# led_flasher_v1.net
KiCad netlist of a schematic drawn in EAGLE
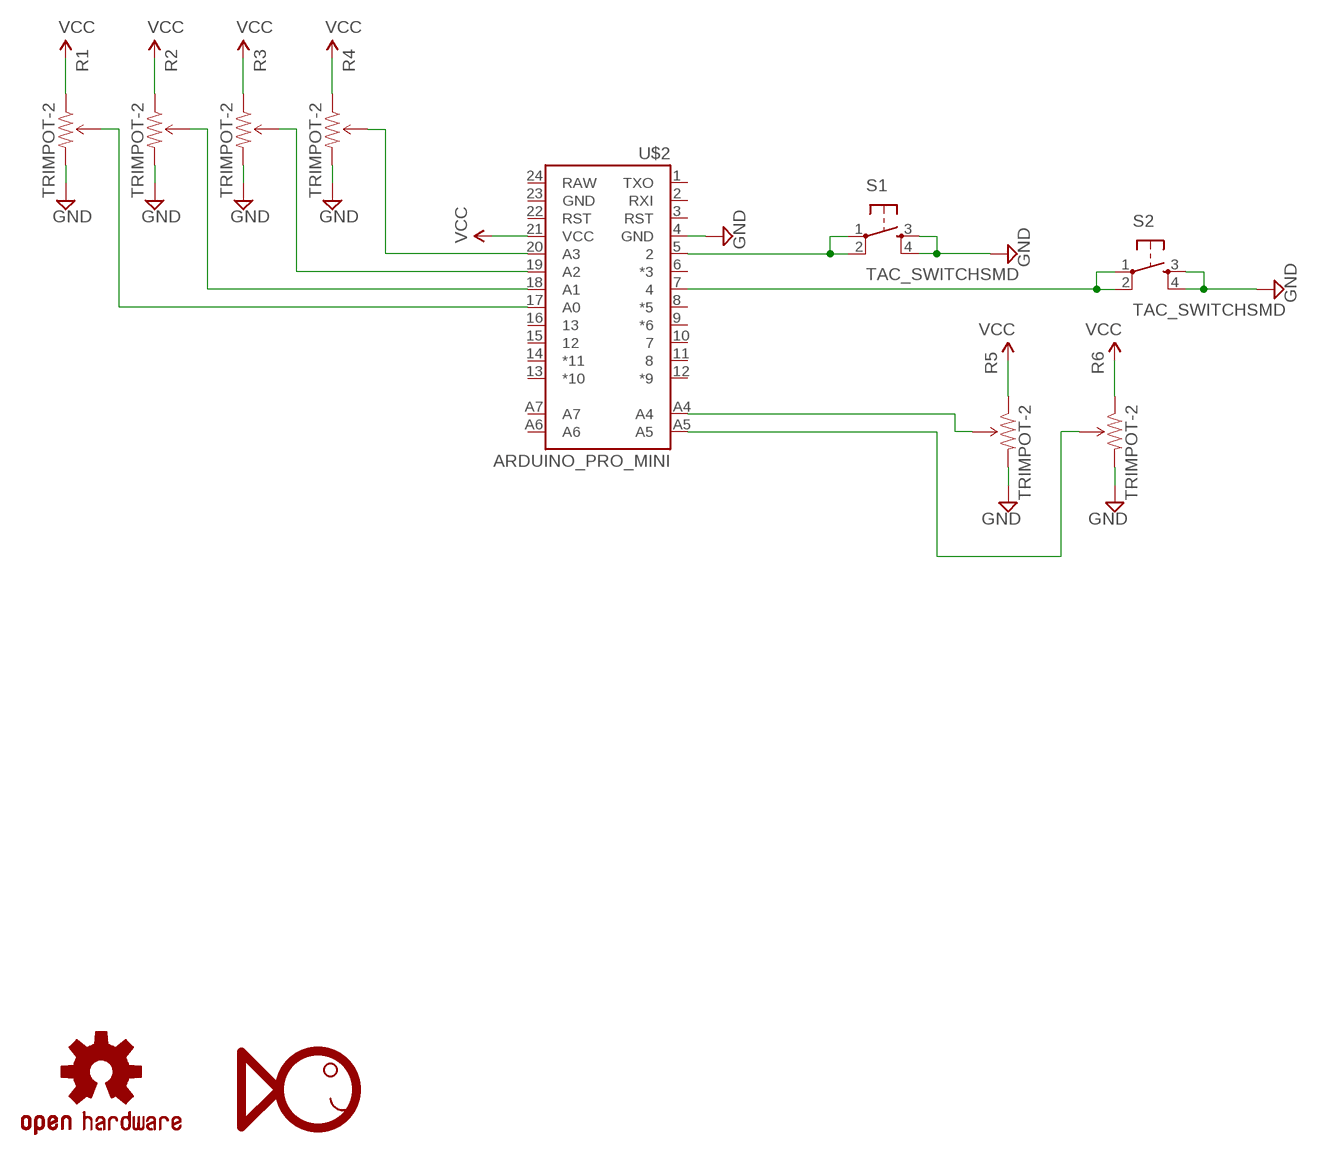
[diagram p0: schematic, sheet 1]

(export (version "E")
  (design (tool "Eeschema 10.0.6"))
  (components
    (comp (ref "LOGO1")
      (value "OSHW-LOGOS")
      (footprint "eagle-import:OSHW-LOGO-S")
      (libsource (lib "eagle-import") (part "OSHW-LOGOS"))
    )
    (comp (ref "R1")
      (value "TRIMPOT-2")
      (footprint "eagle-import:TRIMPOT_TC33")
      (libsource (lib "eagle-import") (part "TRIMPOT-2"))
    )
    (comp (ref "R2")
      (value "TRIMPOT-2")
      (footprint "eagle-import:TRIMPOT_TC33")
      (libsource (lib "eagle-import") (part "TRIMPOT-2"))
    )
    (comp (ref "R3")
      (value "TRIMPOT-2")
      (footprint "eagle-import:TRIMPOT_TC33")
      (libsource (lib "eagle-import") (part "TRIMPOT-2"))
    )
    (comp (ref "R4")
      (value "TRIMPOT-2")
      (footprint "eagle-import:TRIMPOT_TC33")
      (libsource (lib "eagle-import") (part "TRIMPOT-2"))
    )
    (comp (ref "R5")
      (value "TRIMPOT-2")
      (footprint "eagle-import:TRIMPOT_TC33")
      (libsource (lib "eagle-import") (part "TRIMPOT-2"))
    )
    (comp (ref "R6")
      (value "TRIMPOT-2")
      (footprint "eagle-import:TRIMPOT_TC33")
      (libsource (lib "eagle-import") (part "TRIMPOT-2"))
    )
    (comp (ref "S1")
      (value "TAC_SWITCHSMD")
      (footprint "eagle-import:TACTILE-SWITCH-SMD")
      (libsource (lib "eagle-import") (part "TAC_SWITCHSMD"))
    )
    (comp (ref "S2")
      (value "TAC_SWITCHSMD")
      (footprint "eagle-import:TACTILE-SWITCH-SMD")
      (libsource (lib "eagle-import") (part "TAC_SWITCHSMD"))
    )
    (comp (ref "U$1")
      (value "FHI_LOGO")
      (footprint "eagle-import:FHI_LOGO")
      (libsource (lib "eagle-import") (part "FHI_LOGO"))
    )
    (comp (ref "U$2")
      (value "ARDUINO_PRO_MINI")
      (footprint "eagle-import:ARDUINO_PRO_MINI")
      (libsource (lib "eagle-import") (part "ARDUINO_PRO_MINI"))
    )
  )
  (nets
    (net (code "1") (name "GND") (class "Default")
      (node (ref "R1") (pin "3") (pinfunction "CW_3") (pintype "passive"))
      (node (ref "R2") (pin "3") (pinfunction "CW_3") (pintype "passive"))
      (node (ref "R3") (pin "3") (pinfunction "CW_3") (pintype "passive"))
      (node (ref "R4") (pin "3") (pinfunction "CW_3") (pintype "passive"))
      (node (ref "R5") (pin "3") (pinfunction "CW_3") (pintype "passive"))
      (node (ref "R6") (pin "3") (pinfunction "CW_3") (pintype "passive"))
      (node (ref "S1") (pin "3") (pinfunction "3_3") (pintype "passive"))
      (node (ref "S1") (pin "4") (pinfunction "4_4") (pintype "passive"))
      (node (ref "S2") (pin "3") (pinfunction "3_3") (pintype "passive"))
      (node (ref "S2") (pin "4") (pinfunction "4_4") (pintype "passive"))
      (node (ref "U$2") (pin "4") (pinfunction "GND_4") (pintype "bidirectional"))
    )
    (net (code "2") (name "Net-(R1-WIPER)") (class "Default")
      (node (ref "R1") (pin "2") (pinfunction "WIPER_2") (pintype "passive"))
      (node (ref "U$2") (pin "17") (pinfunction "A0_17") (pintype "bidirectional"))
    )
    (net (code "3") (name "Net-(R2-WIPER)") (class "Default")
      (node (ref "R2") (pin "2") (pinfunction "WIPER_2") (pintype "passive"))
      (node (ref "U$2") (pin "18") (pinfunction "A1_18") (pintype "bidirectional"))
    )
    (net (code "4") (name "Net-(R3-WIPER)") (class "Default")
      (node (ref "R3") (pin "2") (pinfunction "WIPER_2") (pintype "passive"))
      (node (ref "U$2") (pin "19") (pinfunction "A2_19") (pintype "bidirectional"))
    )
    (net (code "5") (name "Net-(R4-WIPER)") (class "Default")
      (node (ref "R4") (pin "2") (pinfunction "WIPER_2") (pintype "passive"))
      (node (ref "U$2") (pin "20") (pinfunction "A3_20") (pintype "bidirectional"))
    )
    (net (code "6") (name "Net-(R5-WIPER)") (class "Default")
      (node (ref "R5") (pin "2") (pinfunction "WIPER_2") (pintype "passive"))
      (node (ref "U$2") (pin "A4") (pinfunction "A4_A4") (pintype "bidirectional"))
    )
    (net (code "7") (name "Net-(R6-WIPER)") (class "Default")
      (node (ref "R6") (pin "2") (pinfunction "WIPER_2") (pintype "passive"))
      (node (ref "U$2") (pin "A5") (pinfunction "A5_A5") (pintype "bidirectional"))
    )
    (net (code "8") (name "Net-(U$2-2)") (class "Default")
      (node (ref "S1") (pin "1") (pinfunction "1_1") (pintype "passive"))
      (node (ref "S1") (pin "2") (pinfunction "2_2") (pintype "passive"))
      (node (ref "U$2") (pin "5") (pinfunction "2_5") (pintype "bidirectional"))
    )
    (net (code "9") (name "Net-(U$2-4)") (class "Default")
      (node (ref "S2") (pin "1") (pinfunction "1_1") (pintype "passive"))
      (node (ref "S2") (pin "2") (pinfunction "2_2") (pintype "passive"))
      (node (ref "U$2") (pin "7") (pinfunction "4_7") (pintype "bidirectional"))
    )
    (net (code "10") (name "VCC") (class "Default")
      (node (ref "R1") (pin "1") (pinfunction "CCW_1") (pintype "passive"))
      (node (ref "R2") (pin "1") (pinfunction "CCW_1") (pintype "passive"))
      (node (ref "R3") (pin "1") (pinfunction "CCW_1") (pintype "passive"))
      (node (ref "R4") (pin "1") (pinfunction "CCW_1") (pintype "passive"))
      (node (ref "R5") (pin "1") (pinfunction "CCW_1") (pintype "passive"))
      (node (ref "R6") (pin "1") (pinfunction "CCW_1") (pintype "passive"))
      (node (ref "U$2") (pin "21") (pinfunction "VCC_21") (pintype "bidirectional"))
    )
    (net (code "11") (name "unconnected-(U$2-*3-Pad6)") (class "Default")
      (node (ref "U$2") (pin "6") (pinfunction "*3_6") (pintype "bidirectional"))
    )
    (net (code "12") (name "unconnected-(U$2-*5-Pad8)") (class "Default")
      (node (ref "U$2") (pin "8") (pinfunction "*5_8") (pintype "bidirectional"))
    )
    (net (code "13") (name "unconnected-(U$2-*6-Pad9)") (class "Default")
      (node (ref "U$2") (pin "9") (pinfunction "*6_9") (pintype "bidirectional"))
    )
    (net (code "14") (name "unconnected-(U$2-*9-Pad12)") (class "Default")
      (node (ref "U$2") (pin "12") (pinfunction "*9_12") (pintype "bidirectional"))
    )
    (net (code "15") (name "unconnected-(U$2-*10-Pad13)") (class "Default")
      (node (ref "U$2") (pin "13") (pinfunction "*10_13") (pintype "bidirectional"))
    )
    (net (code "16") (name "unconnected-(U$2-*11-Pad14)") (class "Default")
      (node (ref "U$2") (pin "14") (pinfunction "*11_14") (pintype "bidirectional"))
    )
    (net (code "17") (name "unconnected-(U$2-7-Pad10)") (class "Default")
      (node (ref "U$2") (pin "10") (pinfunction "7_10") (pintype "bidirectional"))
    )
    (net (code "18") (name "unconnected-(U$2-8-Pad11)") (class "Default")
      (node (ref "U$2") (pin "11") (pinfunction "8_11") (pintype "bidirectional"))
    )
    (net (code "19") (name "unconnected-(U$2-12-Pad15)") (class "Default")
      (node (ref "U$2") (pin "15") (pinfunction "12_15") (pintype "bidirectional"))
    )
    (net (code "20") (name "unconnected-(U$2-13-Pad16)") (class "Default")
      (node (ref "U$2") (pin "16") (pinfunction "13_16") (pintype "bidirectional"))
    )
    (net (code "21") (name "unconnected-(U$2-GND-Pad23)") (class "Default")
      (node (ref "U$2") (pin "23") (pinfunction "GND_23") (pintype "bidirectional"))
    )
    (net (code "22") (name "unconnected-(U$2-PadA6)") (class "Default")
      (node (ref "U$2") (pin "A6") (pinfunction "A6_A6") (pintype "bidirectional"))
    )
    (net (code "23") (name "unconnected-(U$2-PadA7)") (class "Default")
      (node (ref "U$2") (pin "A7") (pinfunction "A7_A7") (pintype "bidirectional"))
    )
    (net (code "24") (name "unconnected-(U$2-RAW-Pad24)") (class "Default")
      (node (ref "U$2") (pin "24") (pinfunction "RAW_24") (pintype "bidirectional"))
    )
    (net (code "25") (name "unconnected-(U$2-RST-Pad3)") (class "Default")
      (node (ref "U$2") (pin "3") (pinfunction "RST_3") (pintype "bidirectional"))
    )
    (net (code "26") (name "unconnected-(U$2-RST-Pad22)") (class "Default")
      (node (ref "U$2") (pin "22") (pinfunction "RST_22") (pintype "bidirectional"))
    )
    (net (code "27") (name "unconnected-(U$2-RXI-Pad2)") (class "Default")
      (node (ref "U$2") (pin "2") (pinfunction "RXI_2") (pintype "bidirectional"))
    )
    (net (code "28") (name "unconnected-(U$2-TXO-Pad1)") (class "Default")
      (node (ref "U$2") (pin "1") (pinfunction "TXO_1") (pintype "bidirectional"))
    )
  )
)
